# PocaLFO.net
KiCad netlist of a schematic drawn in EAGLE
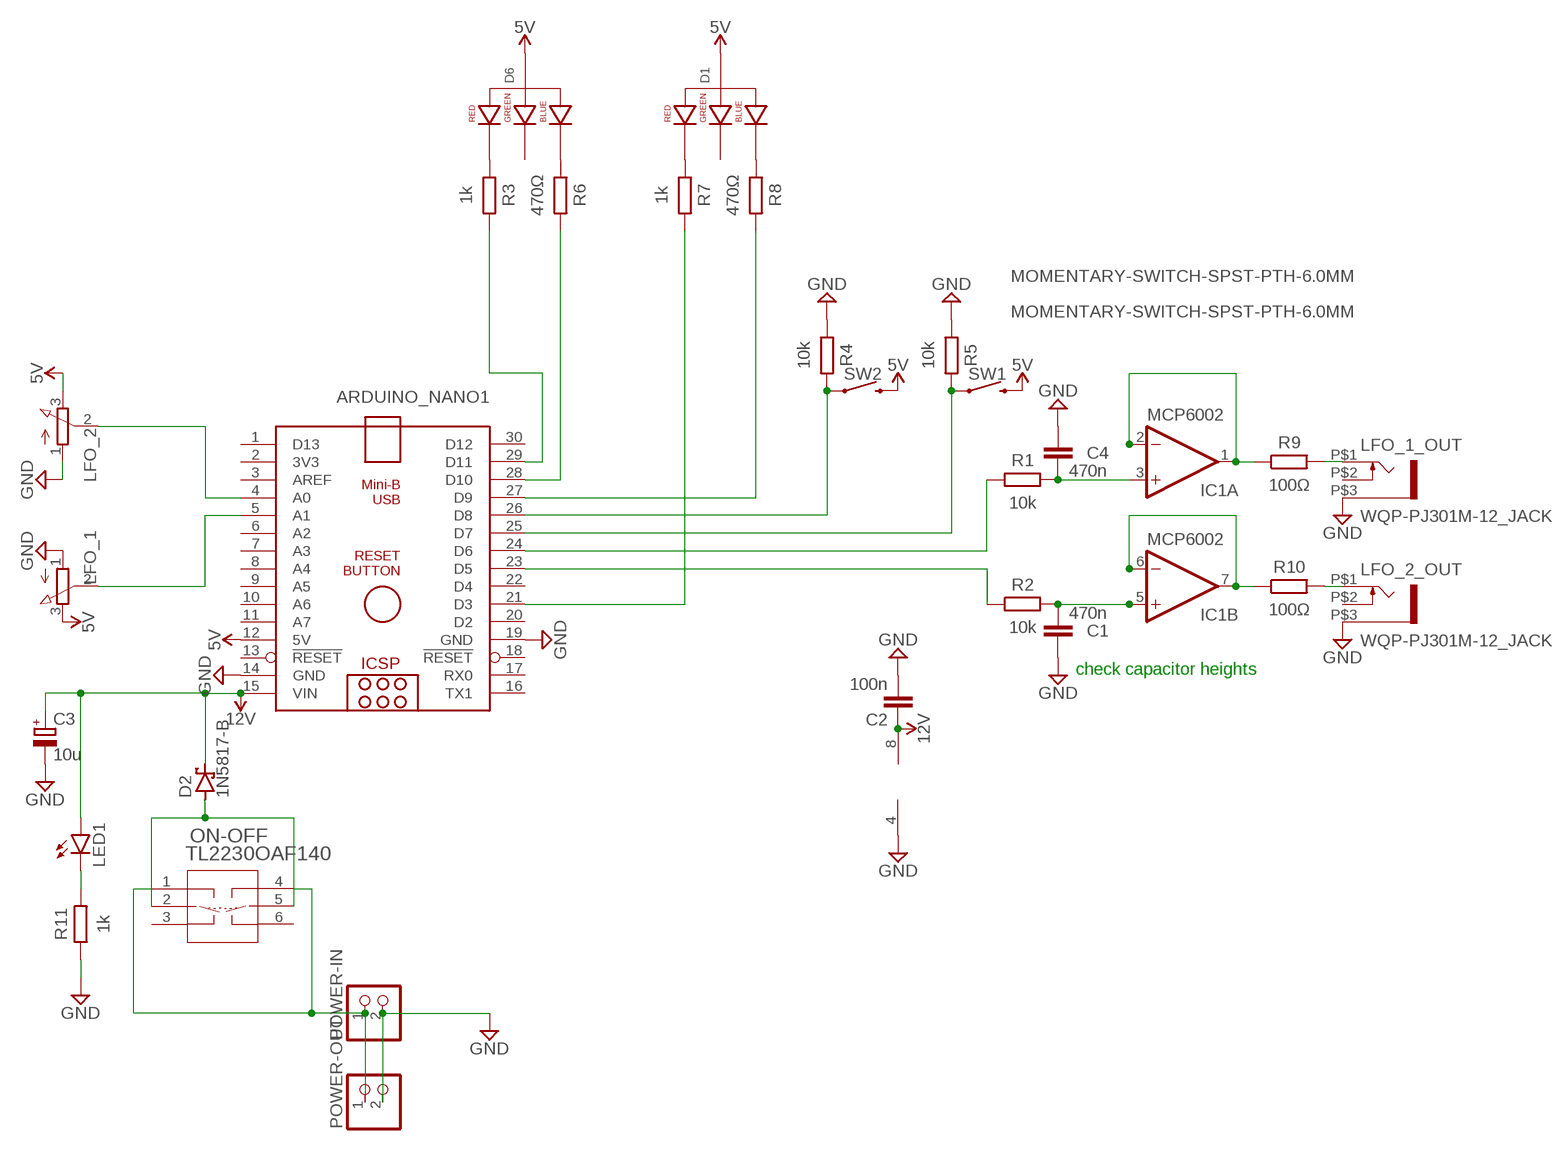
[diagram p0: schematic, sheet 1]

(export (version "E")
  (design (tool "Eeschema 10.0.6"))
  (components
    (comp (ref "ARDUINO_NANO1")
      (value "ARDUINO_NANO")
      (footprint "eagle-import:ARDUINO_NANO")
      (libsource (lib "eagle-import") (part "ARDUINO_NANO"))
    )
    (comp (ref "C1")
      (value "470n")
      (footprint "eagle-import:C5B3.5")
      (libsource (lib "eagle-import") (part "C5/3.5"))
    )
    (comp (ref "C2")
      (value "100n")
      (footprint "eagle-import:C2.5-4")
      (libsource (lib "eagle-import") (part "C2.5/4"))
    )
    (comp (ref "C3")
      (value "10u")
      (footprint "eagle-import:E5-5")
      (libsource (lib "eagle-import") (part "CPOL-EUE5-5"))
    )
    (comp (ref "C4")
      (value "470n")
      (footprint "eagle-import:C5B3.5")
      (libsource (lib "eagle-import") (part "C5/3.5"))
    )
    (comp (ref "D1")
      (value "LED-RGB-CA-THRUCLEAR")
      (footprint "eagle-import:LED-RGB-THRU")
      (libsource (lib "eagle-import") (part "LED-RGB-CA-THRUCLEAR"))
    )
    (comp (ref "D2")
      (value "1N5817-B")
      (footprint "eagle-import:DO41-7.6")
      (libsource (lib "eagle-import") (part "1N5817-B"))
    )
    (comp (ref "D6")
      (value "LED-RGB-CA-THRUCLEAR")
      (footprint "eagle-import:LED-RGB-THRU")
      (libsource (lib "eagle-import") (part "LED-RGB-CA-THRUCLEAR"))
    )
    (comp (ref "IC1")
      (value "MCP6002")
      (footprint "eagle-import:DIL08")
      (libsource (lib "eagle-import") (part "TL072P"))
    )
    (comp (ref "LED1")
      (value "LED3MM")
      (footprint "eagle-import:LED3MM")
      (libsource (lib "eagle-import") (part "LED3MM"))
    )
    (comp (ref "LFO_1")
      (value "10kb")
      (footprint "eagle-import:EVUFXM")
      (libsource (lib "eagle-import") (part "EVUMF3"))
    )
    (comp (ref "LFO_1_OUT")
      (value "WQP-PJ301M-12_JACK")
      (footprint "eagle-import:WQP-PJ301M-12_JACK")
      (libsource (lib "eagle-import") (part "WQP-PJ301M-12_JACK"))
    )
    (comp (ref "LFO_2")
      (value "10kb")
      (footprint "eagle-import:EVUFXM")
      (libsource (lib "eagle-import") (part "EVUMF3"))
    )
    (comp (ref "LFO_2_OUT")
      (value "WQP-PJ301M-12_JACK")
      (footprint "eagle-import:WQP-PJ301M-12_JACK")
      (libsource (lib "eagle-import") (part "WQP-PJ301M-12_JACK"))
    )
    (comp (ref "ON-OFF")
      (value "TL2230OAF140")
      (footprint "eagle-import:TL2230_EWI")
      (fields (field (name "COPYRIGHT") "Copyright (C) 2023 Ultra Librarian. All rights reserved."))
      (libsource (lib "eagle-import") (part "TL2230OAF140"))
    )
    (comp (ref "POWER-IN")
      (value "PINHD-1X2")
      (footprint "eagle-import:1X02")
      (libsource (lib "eagle-import") (part "PINHD-1X2"))
    )
    (comp (ref "POWER-OUT")
      (value "PINHD-1X2")
      (footprint "eagle-import:1X02")
      (libsource (lib "eagle-import") (part "PINHD-1X2"))
    )
    (comp (ref "R1")
      (value "10k")
      (footprint "eagle-import:0207_10")
      (libsource (lib "eagle-import") (part "R-EU_0207/10"))
    )
    (comp (ref "R2")
      (value "10k")
      (footprint "eagle-import:0207_10")
      (libsource (lib "eagle-import") (part "R-EU_0207/10"))
    )
    (comp (ref "R3")
      (value "1k")
      (footprint "eagle-import:0207_10")
      (libsource (lib "eagle-import") (part "R-EU_0207/10"))
    )
    (comp (ref "R4")
      (value "10k")
      (footprint "eagle-import:0207_10")
      (libsource (lib "eagle-import") (part "R-EU_0207/10"))
    )
    (comp (ref "R5")
      (value "10k")
      (footprint "eagle-import:0207_10")
      (libsource (lib "eagle-import") (part "R-EU_0207/10"))
    )
    (comp (ref "R6")
      (value "470Ω")
      (footprint "eagle-import:0207_10")
      (libsource (lib "eagle-import") (part "R-EU_0207/10"))
    )
    (comp (ref "R7")
      (value "1k")
      (footprint "eagle-import:0207_10")
      (libsource (lib "eagle-import") (part "R-EU_0207/10"))
    )
    (comp (ref "R8")
      (value "470Ω")
      (footprint "eagle-import:0207_10")
      (libsource (lib "eagle-import") (part "R-EU_0207/10"))
    )
    (comp (ref "R9")
      (value "100Ω")
      (footprint "eagle-import:0207_10")
      (libsource (lib "eagle-import") (part "R-EU_0207/10"))
    )
    (comp (ref "R10")
      (value "100Ω")
      (footprint "eagle-import:0207_10")
      (libsource (lib "eagle-import") (part "R-EU_0207/10"))
    )
    (comp (ref "R11")
      (value "1k")
      (footprint "eagle-import:0207_10")
      (libsource (lib "eagle-import") (part "R-EU_0207/10"))
    )
    (comp (ref "SW1")
      (value "MOMENTARY-SWITCH-SPST-PTH-6.0MM")
      (footprint "eagle-import:TACTILE_SWITCH_PTH_6.0MM")
      (libsource (lib "eagle-import") (part "MOMENTARY-SWITCH-SPST-PTH-6.0MM"))
    )
    (comp (ref "SW2")
      (value "MOMENTARY-SWITCH-SPST-PTH-6.0MM")
      (footprint "eagle-import:TACTILE_SWITCH_PTH_6.0MM")
      (libsource (lib "eagle-import") (part "MOMENTARY-SWITCH-SPST-PTH-6.0MM"))
    )
  )
  (nets
    (net (code "1") (name "5V") (class "Default")
      (node (ref "ARDUINO_NANO1") (pin "12") (pinfunction "5V_12") (pintype "power_in"))
      (node (ref "D1") (pin "2") (pinfunction "ANODE_2") (pintype "bidirectional"))
      (node (ref "D6") (pin "2") (pinfunction "ANODE_2") (pintype "bidirectional"))
      (node (ref "LFO_1") (pin "3") (pinfunction "E_3") (pintype "passive"))
      (node (ref "LFO_2") (pin "3") (pinfunction "E_3") (pintype "passive"))
      (node (ref "SW1") (pin "3") (pinfunction "2_3") (pintype "passive"))
      (node (ref "SW2") (pin "3") (pinfunction "2_3") (pintype "passive"))
    )
    (net (code "2") (name "12V") (class "Default")
      (node (ref "ARDUINO_NANO1") (pin "15") (pinfunction "VIN_15") (pintype "power_in"))
      (node (ref "C2") (pin "1") (pinfunction "1_1") (pintype "passive"))
      (node (ref "C3") (pin "+") (pinfunction "+_+") (pintype "passive"))
      (node (ref "D2") (pin "C") (pinfunction "C_C") (pintype "passive"))
      (node (ref "IC1") (pin "8") (pinfunction "V+_8") (pintype "power_in"))
      (node (ref "LED1") (pin "A") (pinfunction "A_A") (pintype "passive"))
    )
    (net (code "3") (name "GND") (class "Default")
      (node (ref "ARDUINO_NANO1") (pin "14") (pinfunction "GND_14") (pintype "power_in"))
      (node (ref "ARDUINO_NANO1") (pin "19") (pinfunction "GND_19") (pintype "power_in"))
      (node (ref "C1") (pin "2") (pinfunction "2_2") (pintype "passive"))
      (node (ref "C2") (pin "2") (pinfunction "2_2") (pintype "passive"))
      (node (ref "C3") (pin "-") (pinfunction "-_-") (pintype "passive"))
      (node (ref "C4") (pin "1") (pinfunction "1_1") (pintype "passive"))
      (node (ref "IC1") (pin "4") (pinfunction "V-_4") (pintype "power_in"))
      (node (ref "LFO_1") (pin "1") (pinfunction "A_1") (pintype "passive"))
      (node (ref "LFO_1_OUT") (pin "P$3") (pinfunction "1_P$3") (pintype "passive"))
      (node (ref "LFO_2") (pin "1") (pinfunction "A_1") (pintype "passive"))
      (node (ref "LFO_2_OUT") (pin "P$3") (pinfunction "1_P$3") (pintype "passive"))
      (node (ref "POWER-IN") (pin "2") (pinfunction "2_2") (pintype "passive"))
      (node (ref "POWER-OUT") (pin "2") (pinfunction "2_2") (pintype "passive"))
      (node (ref "R11") (pin "1") (pinfunction "1_1") (pintype "passive"))
      (node (ref "R4") (pin "1") (pinfunction "1_1") (pintype "passive"))
      (node (ref "R5") (pin "1") (pinfunction "1_1") (pintype "passive"))
    )
    (net (code "4") (name "Net-(ARDUINO_NANO1-A0)") (class "Default")
      (node (ref "ARDUINO_NANO1") (pin "4") (pinfunction "A0_4") (pintype "bidirectional"))
      (node (ref "LFO_2") (pin "2") (pinfunction "S_2") (pintype "passive"))
    )
    (net (code "5") (name "Net-(ARDUINO_NANO1-A1)") (class "Default")
      (node (ref "ARDUINO_NANO1") (pin "5") (pinfunction "A1_5") (pintype "bidirectional"))
      (node (ref "LFO_1") (pin "2") (pinfunction "S_2") (pintype "passive"))
    )
    (net (code "6") (name "Net-(ARDUINO_NANO1-D3)") (class "Default")
      (node (ref "ARDUINO_NANO1") (pin "21") (pinfunction "D3_21") (pintype "bidirectional"))
      (node (ref "R7") (pin "2") (pinfunction "2_2") (pintype "passive"))
    )
    (net (code "7") (name "Net-(ARDUINO_NANO1-D5)") (class "Default")
      (node (ref "ARDUINO_NANO1") (pin "23") (pinfunction "D5_23") (pintype "bidirectional"))
      (node (ref "R2") (pin "1") (pinfunction "1_1") (pintype "passive"))
    )
    (net (code "8") (name "Net-(ARDUINO_NANO1-D6)") (class "Default")
      (node (ref "ARDUINO_NANO1") (pin "24") (pinfunction "D6_24") (pintype "bidirectional"))
      (node (ref "R1") (pin "1") (pinfunction "1_1") (pintype "passive"))
    )
    (net (code "9") (name "Net-(ARDUINO_NANO1-D7)") (class "Default")
      (node (ref "ARDUINO_NANO1") (pin "25") (pinfunction "D7_25") (pintype "bidirectional"))
      (node (ref "R5") (pin "2") (pinfunction "2_2") (pintype "passive"))
      (node (ref "SW1") (pin "1") (pinfunction "1_1") (pintype "passive"))
    )
    (net (code "10") (name "Net-(ARDUINO_NANO1-D8)") (class "Default")
      (node (ref "ARDUINO_NANO1") (pin "26") (pinfunction "D8_26") (pintype "bidirectional"))
      (node (ref "R4") (pin "2") (pinfunction "2_2") (pintype "passive"))
      (node (ref "SW2") (pin "1") (pinfunction "1_1") (pintype "passive"))
    )
    (net (code "11") (name "Net-(ARDUINO_NANO1-D9)") (class "Default")
      (node (ref "ARDUINO_NANO1") (pin "27") (pinfunction "D9_27") (pintype "bidirectional"))
      (node (ref "R8") (pin "2") (pinfunction "2_2") (pintype "passive"))
    )
    (net (code "12") (name "Net-(ARDUINO_NANO1-D10)") (class "Default")
      (node (ref "ARDUINO_NANO1") (pin "28") (pinfunction "D10_28") (pintype "bidirectional"))
      (node (ref "R6") (pin "2") (pinfunction "2_2") (pintype "passive"))
    )
    (net (code "13") (name "Net-(ARDUINO_NANO1-D11)") (class "Default")
      (node (ref "ARDUINO_NANO1") (pin "29") (pinfunction "D11_29") (pintype "bidirectional"))
      (node (ref "R3") (pin "2") (pinfunction "2_2") (pintype "passive"))
    )
    (net (code "14") (name "Net-(D1-BLUE_CATHODE)") (class "Default")
      (node (ref "D1") (pin "4") (pinfunction "BLUE_CATHODE_4") (pintype "bidirectional"))
      (node (ref "R8") (pin "1") (pinfunction "1_1") (pintype "passive"))
    )
    (net (code "15") (name "Net-(D1-RED_CATHODE)") (class "Default")
      (node (ref "D1") (pin "1") (pinfunction "RED_CATHODE_1") (pintype "bidirectional"))
      (node (ref "R7") (pin "1") (pinfunction "1_1") (pintype "passive"))
    )
    (net (code "16") (name "Net-(D2-PadA)") (class "Default")
      (node (ref "D2") (pin "A") (pinfunction "A_A") (pintype "passive"))
      (node (ref "ON-OFF") (pin "2") (pinfunction "2_2") (pintype "passive"))
      (node (ref "ON-OFF") (pin "5") (pinfunction "5_5") (pintype "passive"))
    )
    (net (code "17") (name "Net-(D6-BLUE_CATHODE)") (class "Default")
      (node (ref "D6") (pin "4") (pinfunction "BLUE_CATHODE_4") (pintype "bidirectional"))
      (node (ref "R6") (pin "1") (pinfunction "1_1") (pintype "passive"))
    )
    (net (code "18") (name "Net-(D6-RED_CATHODE)") (class "Default")
      (node (ref "D6") (pin "1") (pinfunction "RED_CATHODE_1") (pintype "bidirectional"))
      (node (ref "R3") (pin "1") (pinfunction "1_1") (pintype "passive"))
    )
    (net (code "19") (name "Net-(IC1A-+IN)") (class "Default")
      (node (ref "C4") (pin "2") (pinfunction "2_2") (pintype "passive"))
      (node (ref "IC1") (pin "3") (pinfunction "+IN_3") (pintype "input"))
      (node (ref "R1") (pin "2") (pinfunction "2_2") (pintype "passive"))
    )
    (net (code "20") (name "Net-(IC1A--IN)") (class "Default")
      (node (ref "IC1") (pin "1") (pinfunction "OUT_1") (pintype "output"))
      (node (ref "IC1") (pin "2") (pinfunction "-IN_2") (pintype "input"))
      (node (ref "R9") (pin "1") (pinfunction "1_1") (pintype "passive"))
    )
    (net (code "21") (name "Net-(IC1B-+IN)") (class "Default")
      (node (ref "C1") (pin "1") (pinfunction "1_1") (pintype "passive"))
      (node (ref "IC1") (pin "5") (pinfunction "+IN_5") (pintype "input"))
      (node (ref "R2") (pin "2") (pinfunction "2_2") (pintype "passive"))
    )
    (net (code "22") (name "Net-(IC1B--IN)") (class "Default")
      (node (ref "IC1") (pin "6") (pinfunction "-IN_6") (pintype "input"))
      (node (ref "IC1") (pin "7") (pinfunction "OUT_7") (pintype "output"))
      (node (ref "R10") (pin "1") (pinfunction "1_1") (pintype "passive"))
    )
    (net (code "23") (name "Net-(LED1-C)") (class "Default")
      (node (ref "LED1") (pin "K") (pinfunction "C_K") (pintype "passive"))
      (node (ref "R11") (pin "2") (pinfunction "2_2") (pintype "passive"))
    )
    (net (code "24") (name "Net-(LFO_1_OUT-2)") (class "Default")
      (node (ref "LFO_1_OUT") (pin "P$1") (pinfunction "2_P$1") (pintype "passive"))
      (node (ref "R9") (pin "2") (pinfunction "2_2") (pintype "passive"))
    )
    (net (code "25") (name "Net-(LFO_2_OUT-2)") (class "Default")
      (node (ref "LFO_2_OUT") (pin "P$1") (pinfunction "2_P$1") (pintype "passive"))
      (node (ref "R10") (pin "2") (pinfunction "2_2") (pintype "passive"))
    )
    (net (code "26") (name "Net-(ON-OFF-Pad1)") (class "Default")
      (node (ref "ON-OFF") (pin "1") (pinfunction "1_1") (pintype "passive"))
      (node (ref "ON-OFF") (pin "4") (pinfunction "4_4") (pintype "passive"))
      (node (ref "POWER-IN") (pin "1") (pinfunction "1_1") (pintype "passive"))
      (node (ref "POWER-OUT") (pin "1") (pinfunction "1_1") (pintype "passive"))
    )
    (net (code "27") (name "unconnected-(ARDUINO_NANO1-3V3-Pad2)") (class "Default")
      (node (ref "ARDUINO_NANO1") (pin "2") (pinfunction "3V3_2") (pintype "output"))
    )
    (net (code "28") (name "unconnected-(ARDUINO_NANO1-A2-Pad6)") (class "Default")
      (node (ref "ARDUINO_NANO1") (pin "6") (pinfunction "A2_6") (pintype "bidirectional"))
    )
    (net (code "29") (name "unconnected-(ARDUINO_NANO1-A3-Pad7)") (class "Default")
      (node (ref "ARDUINO_NANO1") (pin "7") (pinfunction "A3_7") (pintype "bidirectional"))
    )
    (net (code "30") (name "unconnected-(ARDUINO_NANO1-A4-Pad8)") (class "Default")
      (node (ref "ARDUINO_NANO1") (pin "8") (pinfunction "A4_8") (pintype "bidirectional"))
    )
    (net (code "31") (name "unconnected-(ARDUINO_NANO1-A5-Pad9)") (class "Default")
      (node (ref "ARDUINO_NANO1") (pin "9") (pinfunction "A5_9") (pintype "bidirectional"))
    )
    (net (code "32") (name "unconnected-(ARDUINO_NANO1-A6-Pad10)") (class "Default")
      (node (ref "ARDUINO_NANO1") (pin "10") (pinfunction "A6_10") (pintype "bidirectional"))
    )
    (net (code "33") (name "unconnected-(ARDUINO_NANO1-A7-Pad11)") (class "Default")
      (node (ref "ARDUINO_NANO1") (pin "11") (pinfunction "A7_11") (pintype "bidirectional"))
    )
    (net (code "34") (name "unconnected-(ARDUINO_NANO1-AREF-Pad3)") (class "Default")
      (node (ref "ARDUINO_NANO1") (pin "3") (pinfunction "AREF_3") (pintype "input"))
    )
    (net (code "35") (name "unconnected-(ARDUINO_NANO1-D2-Pad20)") (class "Default")
      (node (ref "ARDUINO_NANO1") (pin "20") (pinfunction "D2_20") (pintype "bidirectional"))
    )
    (net (code "36") (name "unconnected-(ARDUINO_NANO1-D4-Pad22)") (class "Default")
      (node (ref "ARDUINO_NANO1") (pin "22") (pinfunction "D4_22") (pintype "bidirectional"))
    )
    (net (code "37") (name "unconnected-(ARDUINO_NANO1-D12-Pad30)") (class "Default")
      (node (ref "ARDUINO_NANO1") (pin "30") (pinfunction "D12_30") (pintype "bidirectional"))
    )
    (net (code "38") (name "unconnected-(ARDUINO_NANO1-D13-Pad1)") (class "Default")
      (node (ref "ARDUINO_NANO1") (pin "1") (pinfunction "D13_1") (pintype "bidirectional"))
    )
    (net (code "39") (name "unconnected-(ARDUINO_NANO1-RX0-Pad17)") (class "Default")
      (node (ref "ARDUINO_NANO1") (pin "17") (pinfunction "RX0_17") (pintype "bidirectional"))
    )
    (net (code "40") (name "unconnected-(ARDUINO_NANO1-TX1-Pad16)") (class "Default")
      (node (ref "ARDUINO_NANO1") (pin "16") (pinfunction "TX1_16") (pintype "bidirectional"))
    )
    (net (code "41") (name "unconnected-(ARDUINO_NANO1-~{RESET}-Pad13)") (class "Default")
      (node (ref "ARDUINO_NANO1") (pin "13") (pinfunction "~{RESET}_13") (pintype "input"))
    )
    (net (code "42") (name "unconnected-(ARDUINO_NANO1-~{RESET}-Pad18)") (class "Default")
      (node (ref "ARDUINO_NANO1") (pin "18") (pinfunction "~{RESET}_18") (pintype "input"))
    )
    (net (code "43") (name "unconnected-(D1-GREEN_CATHODE-Pad3)") (class "Default")
      (node (ref "D1") (pin "3") (pinfunction "GREEN_CATHODE_3") (pintype "bidirectional"))
    )
    (net (code "44") (name "unconnected-(D6-GREEN_CATHODE-Pad3)") (class "Default")
      (node (ref "D6") (pin "3") (pinfunction "GREEN_CATHODE_3") (pintype "bidirectional"))
    )
    (net (code "45") (name "unconnected-(LFO_1_OUT-3-PadP$2)") (class "Default")
      (node (ref "LFO_1_OUT") (pin "P$2") (pinfunction "3_P$2") (pintype "passive"))
    )
    (net (code "46") (name "unconnected-(LFO_2_OUT-3-PadP$2)") (class "Default")
      (node (ref "LFO_2_OUT") (pin "P$2") (pinfunction "3_P$2") (pintype "passive"))
    )
    (net (code "47") (name "unconnected-(ON-OFF-Pad3)") (class "Default")
      (node (ref "ON-OFF") (pin "3") (pinfunction "3_3") (pintype "passive"))
    )
    (net (code "48") (name "unconnected-(ON-OFF-Pad6)") (class "Default")
      (node (ref "ON-OFF") (pin "6") (pinfunction "6_6") (pintype "passive"))
    )
  )
)
